# splitter_board.net
KiCad netlist of a schematic drawn in EAGLE
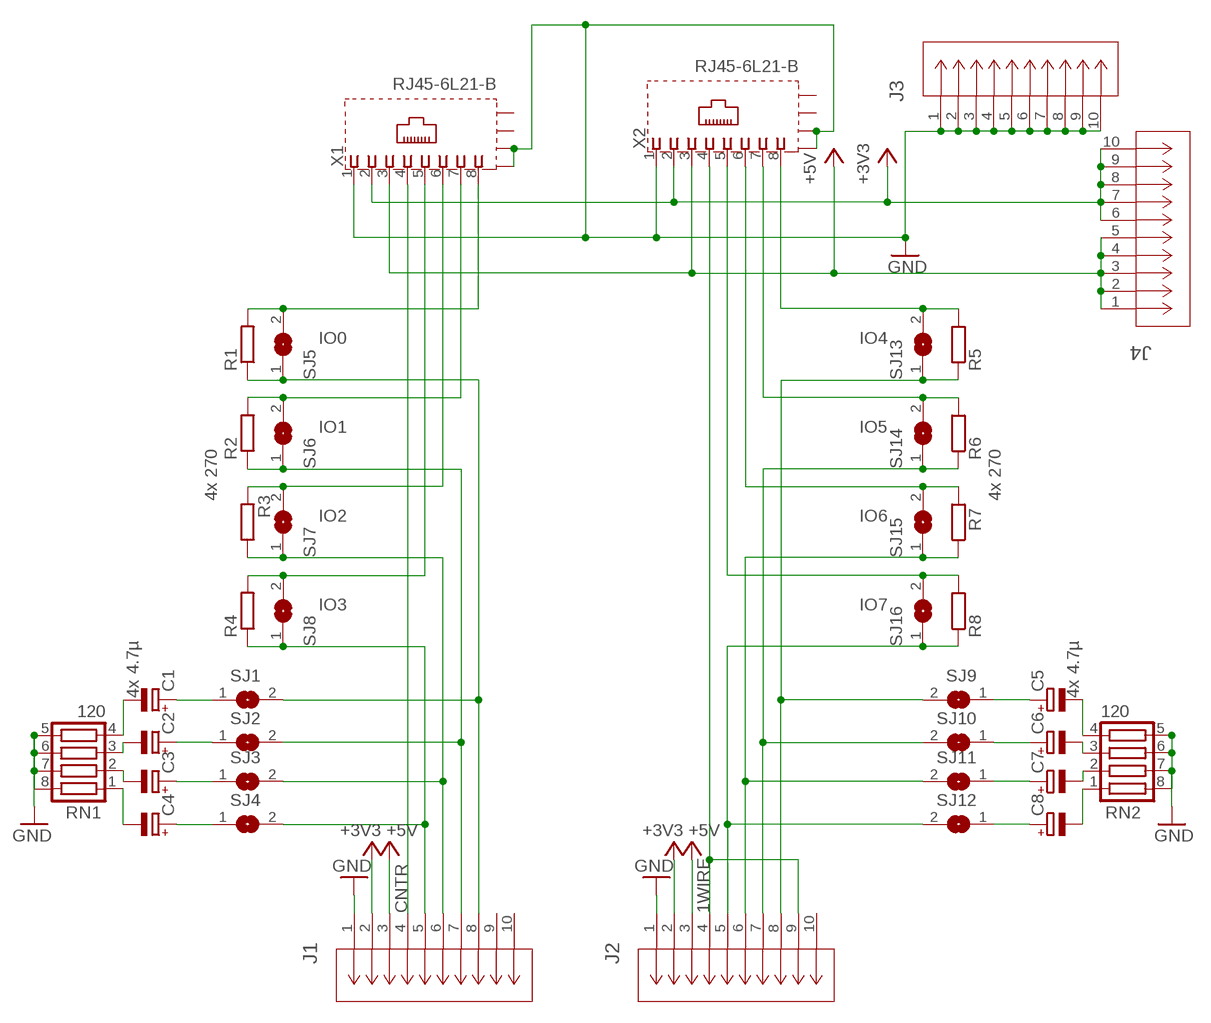
[diagram p0: schematic, sheet 1]

(export (version "E")
  (design (tool "Eeschema 10.0.6"))
  (components
    (comp (ref "C1")
      (value "4.7µ")
      (footprint "eagle-import:A_3216-18R")
      (libsource (lib "eagle-import") (part "CPOL-EUA/3216-18R"))
    )
    (comp (ref "C2")
      (value "4.7µ")
      (footprint "eagle-import:A_3216-18R")
      (libsource (lib "eagle-import") (part "CPOL-EUA/3216-18R"))
    )
    (comp (ref "C3")
      (value "4.7µ")
      (footprint "eagle-import:A_3216-18R")
      (libsource (lib "eagle-import") (part "CPOL-EUA/3216-18R"))
    )
    (comp (ref "C4")
      (value "4.7µ")
      (footprint "eagle-import:A_3216-18R")
      (libsource (lib "eagle-import") (part "CPOL-EUA/3216-18R"))
    )
    (comp (ref "C5")
      (value "4.7µ")
      (footprint "eagle-import:A_3216-18R")
      (libsource (lib "eagle-import") (part "CPOL-EUA/3216-18R"))
    )
    (comp (ref "C6")
      (value "4.7µ")
      (footprint "eagle-import:A_3216-18R")
      (libsource (lib "eagle-import") (part "CPOL-EUA/3216-18R"))
    )
    (comp (ref "C7")
      (value "4.7µ")
      (footprint "eagle-import:A_3216-18R")
      (libsource (lib "eagle-import") (part "CPOL-EUA/3216-18R"))
    )
    (comp (ref "C8")
      (value "4.7µ")
      (footprint "eagle-import:A_3216-18R")
      (libsource (lib "eagle-import") (part "CPOL-EUA/3216-18R"))
    )
    (comp (ref "J1")
      (value "250-410")
      (footprint "eagle-import:CONN_250-410_WAG")
      (fields (field (name "COPYRIGHT") "Copyright (C) 2022 Ultra Librarian. All rights reserved."))
      (libsource (lib "eagle-import") (part "250-410"))
    )
    (comp (ref "J2")
      (value "250-410")
      (footprint "eagle-import:CONN_250-410_WAG")
      (fields (field (name "COPYRIGHT") "Copyright (C) 2022 Ultra Librarian. All rights reserved."))
      (libsource (lib "eagle-import") (part "250-410"))
    )
    (comp (ref "J3")
      (value "250-410")
      (footprint "eagle-import:CONN_250-410_WAG")
      (fields (field (name "COPYRIGHT") "Copyright (C) 2022 Ultra Librarian. All rights reserved."))
      (libsource (lib "eagle-import") (part "250-410"))
    )
    (comp (ref "J4")
      (value "250-410")
      (footprint "eagle-import:CONN_250-410_WAG")
      (fields (field (name "COPYRIGHT") "Copyright (C) 2022 Ultra Librarian. All rights reserved."))
      (libsource (lib "eagle-import") (part "250-410"))
    )
    (comp (ref "R1")
      (value "270")
      (footprint "eagle-import:R0805")
      (libsource (lib "eagle-import") (part "R-EU_R0805"))
    )
    (comp (ref "R2")
      (value "270")
      (footprint "eagle-import:R0805")
      (libsource (lib "eagle-import") (part "R-EU_R0805"))
    )
    (comp (ref "R3")
      (value "270")
      (footprint "eagle-import:R0805")
      (libsource (lib "eagle-import") (part "R-EU_R0805"))
    )
    (comp (ref "R4")
      (value "270")
      (footprint "eagle-import:R0805")
      (libsource (lib "eagle-import") (part "R-EU_R0805"))
    )
    (comp (ref "R5")
      (value "270")
      (footprint "eagle-import:R0805")
      (libsource (lib "eagle-import") (part "R-EU_R0805"))
    )
    (comp (ref "R6")
      (value "270")
      (footprint "eagle-import:R0805")
      (libsource (lib "eagle-import") (part "R-EU_R0805"))
    )
    (comp (ref "R7")
      (value "270")
      (footprint "eagle-import:R0805")
      (libsource (lib "eagle-import") (part "R-EU_R0805"))
    )
    (comp (ref "R8")
      (value "270")
      (footprint "eagle-import:R0805")
      (libsource (lib "eagle-import") (part "R-EU_R0805"))
    )
    (comp (ref "RN1")
      (value "120")
      (footprint "eagle-import:CTS742C083")
      (libsource (lib "eagle-import") (part "CTS742C083"))
    )
    (comp (ref "RN2")
      (value "120")
      (footprint "eagle-import:CTS742C083")
      (libsource (lib "eagle-import") (part "CTS742C083"))
    )
    (comp (ref "SJ1") (value "SJ") (footprint "eagle-import:SJ") (libsource (lib "eagle-import") (part "SJ")))
    (comp (ref "SJ2") (value "SJ") (footprint "eagle-import:SJ") (libsource (lib "eagle-import") (part "SJ")))
    (comp (ref "SJ3") (value "SJ") (footprint "eagle-import:SJ") (libsource (lib "eagle-import") (part "SJ")))
    (comp (ref "SJ4") (value "SJ") (footprint "eagle-import:SJ") (libsource (lib "eagle-import") (part "SJ")))
    (comp (ref "SJ5") (value "SJ") (footprint "eagle-import:SJ") (libsource (lib "eagle-import") (part "SJ")))
    (comp (ref "SJ6") (value "SJ") (footprint "eagle-import:SJ") (libsource (lib "eagle-import") (part "SJ")))
    (comp (ref "SJ7") (value "SJ") (footprint "eagle-import:SJ") (libsource (lib "eagle-import") (part "SJ")))
    (comp (ref "SJ8") (value "SJ") (footprint "eagle-import:SJ") (libsource (lib "eagle-import") (part "SJ")))
    (comp (ref "SJ9") (value "SJ") (footprint "eagle-import:SJ") (libsource (lib "eagle-import") (part "SJ")))
    (comp (ref "SJ10")
      (value "SJ")
      (footprint "eagle-import:SJ")
      (libsource (lib "eagle-import") (part "SJ"))
    )
    (comp (ref "SJ11")
      (value "SJ")
      (footprint "eagle-import:SJ")
      (libsource (lib "eagle-import") (part "SJ"))
    )
    (comp (ref "SJ12")
      (value "SJ")
      (footprint "eagle-import:SJ")
      (libsource (lib "eagle-import") (part "SJ"))
    )
    (comp (ref "SJ13")
      (value "SJ")
      (footprint "eagle-import:SJ")
      (libsource (lib "eagle-import") (part "SJ"))
    )
    (comp (ref "SJ14")
      (value "SJ")
      (footprint "eagle-import:SJ")
      (libsource (lib "eagle-import") (part "SJ"))
    )
    (comp (ref "SJ15")
      (value "SJ")
      (footprint "eagle-import:SJ")
      (libsource (lib "eagle-import") (part "SJ"))
    )
    (comp (ref "SJ16")
      (value "SJ")
      (footprint "eagle-import:SJ")
      (libsource (lib "eagle-import") (part "SJ"))
    )
    (comp (ref "X1")
      (value "RJ45-6L21-B")
      (footprint "eagle-import:RJ45-SHIELD1")
      (libsource (lib "eagle-import") (part "RJ4521-B-6L"))
    )
    (comp (ref "X2")
      (value "RJ45-6L21-B")
      (footprint "eagle-import:RJ45-SHIELD1")
      (libsource (lib "eagle-import") (part "RJ4521-B-6L"))
    )
  )
  (nets
    (net (code "1") (name "+3V3") (class "Default")
      (node (ref "J1") (pin "2") (pinfunction "2_2") (pintype "passive"))
      (node (ref "J2") (pin "2") (pinfunction "2_2") (pintype "passive"))
      (node (ref "J4") (pin "10") (pinfunction "10_10") (pintype "passive"))
      (node (ref "J4") (pin "6") (pinfunction "6_6") (pintype "passive"))
      (node (ref "J4") (pin "7") (pinfunction "7_7") (pintype "passive"))
      (node (ref "J4") (pin "8") (pinfunction "8_8") (pintype "passive"))
      (node (ref "J4") (pin "9") (pinfunction "9_9") (pintype "passive"))
      (node (ref "X1") (pin "2") (pinfunction "2_2") (pintype "passive"))
      (node (ref "X2") (pin "2") (pinfunction "2_2") (pintype "passive"))
    )
    (net (code "2") (name "+5V") (class "Default")
      (node (ref "J1") (pin "3") (pinfunction "3_3") (pintype "passive"))
      (node (ref "J2") (pin "3") (pinfunction "3_3") (pintype "passive"))
      (node (ref "J4") (pin "1") (pinfunction "1_1") (pintype "passive"))
      (node (ref "J4") (pin "2") (pinfunction "2_2") (pintype "passive"))
      (node (ref "J4") (pin "3") (pinfunction "3_3") (pintype "passive"))
      (node (ref "J4") (pin "4") (pinfunction "4_4") (pintype "passive"))
      (node (ref "J4") (pin "5") (pinfunction "5_5") (pintype "passive"))
      (node (ref "X1") (pin "3") (pinfunction "3_3") (pintype "passive"))
      (node (ref "X2") (pin "3") (pinfunction "3_3") (pintype "passive"))
    )
    (net (code "3") (name "/1WIRE") (class "Default")
      (node (ref "J2") (pin "4") (pinfunction "4_4") (pintype "passive"))
      (node (ref "J2") (pin "9") (pinfunction "9_9") (pintype "passive"))
      (node (ref "X2") (pin "4") (pinfunction "4_4") (pintype "passive"))
    )
    (net (code "4") (name "/CNTR") (class "Default")
      (node (ref "J1") (pin "4") (pinfunction "4_4") (pintype "passive"))
      (node (ref "X1") (pin "4") (pinfunction "4_4") (pintype "passive"))
    )
    (net (code "5") (name "/IO0") (class "Default")
      (node (ref "R1") (pin "2") (pinfunction "2_2") (pintype "passive"))
      (node (ref "SJ5") (pin "2") (pinfunction "2_2") (pintype "passive"))
      (node (ref "X1") (pin "8") (pinfunction "8_8") (pintype "passive"))
    )
    (net (code "6") (name "/IO1") (class "Default")
      (node (ref "R2") (pin "2") (pinfunction "2_2") (pintype "passive"))
      (node (ref "SJ6") (pin "2") (pinfunction "2_2") (pintype "passive"))
      (node (ref "X1") (pin "7") (pinfunction "7_7") (pintype "passive"))
    )
    (net (code "7") (name "/IO2") (class "Default")
      (node (ref "R3") (pin "2") (pinfunction "2_2") (pintype "passive"))
      (node (ref "SJ7") (pin "2") (pinfunction "2_2") (pintype "passive"))
      (node (ref "X1") (pin "6") (pinfunction "6_6") (pintype "passive"))
    )
    (net (code "8") (name "/IO3") (class "Default")
      (node (ref "R4") (pin "2") (pinfunction "2_2") (pintype "passive"))
      (node (ref "SJ8") (pin "2") (pinfunction "2_2") (pintype "passive"))
      (node (ref "X1") (pin "5") (pinfunction "5_5") (pintype "passive"))
    )
    (net (code "9") (name "/IO4") (class "Default")
      (node (ref "R5") (pin "2") (pinfunction "2_2") (pintype "passive"))
      (node (ref "SJ13") (pin "2") (pinfunction "2_2") (pintype "passive"))
      (node (ref "X2") (pin "8") (pinfunction "8_8") (pintype "passive"))
    )
    (net (code "10") (name "/IO5") (class "Default")
      (node (ref "R6") (pin "2") (pinfunction "2_2") (pintype "passive"))
      (node (ref "SJ14") (pin "2") (pinfunction "2_2") (pintype "passive"))
      (node (ref "X2") (pin "7") (pinfunction "7_7") (pintype "passive"))
    )
    (net (code "11") (name "/IO6") (class "Default")
      (node (ref "R7") (pin "2") (pinfunction "2_2") (pintype "passive"))
      (node (ref "SJ15") (pin "2") (pinfunction "2_2") (pintype "passive"))
      (node (ref "X2") (pin "6") (pinfunction "6_6") (pintype "passive"))
    )
    (net (code "12") (name "/IO7") (class "Default")
      (node (ref "R8") (pin "2") (pinfunction "2_2") (pintype "passive"))
      (node (ref "SJ16") (pin "2") (pinfunction "2_2") (pintype "passive"))
      (node (ref "X2") (pin "5") (pinfunction "5_5") (pintype "passive"))
    )
    (net (code "13") (name "GND") (class "Default")
      (node (ref "J1") (pin "1") (pinfunction "1_1") (pintype "passive"))
      (node (ref "J2") (pin "1") (pinfunction "1_1") (pintype "passive"))
      (node (ref "J3") (pin "1") (pinfunction "1_1") (pintype "passive"))
      (node (ref "J3") (pin "10") (pinfunction "10_10") (pintype "passive"))
      (node (ref "J3") (pin "2") (pinfunction "2_2") (pintype "passive"))
      (node (ref "J3") (pin "3") (pinfunction "3_3") (pintype "passive"))
      (node (ref "J3") (pin "4") (pinfunction "4_4") (pintype "passive"))
      (node (ref "J3") (pin "5") (pinfunction "5_5") (pintype "passive"))
      (node (ref "J3") (pin "6") (pinfunction "6_6") (pintype "passive"))
      (node (ref "J3") (pin "7") (pinfunction "7_7") (pintype "passive"))
      (node (ref "J3") (pin "8") (pinfunction "8_8") (pintype "passive"))
      (node (ref "J3") (pin "9") (pinfunction "9_9") (pintype "passive"))
      (node (ref "RN1") (pin "5") (pinfunction "5_5") (pintype "passive"))
      (node (ref "RN1") (pin "6") (pinfunction "6_6") (pintype "passive"))
      (node (ref "RN1") (pin "7") (pinfunction "7_7") (pintype "passive"))
      (node (ref "RN1") (pin "8") (pinfunction "8_8") (pintype "passive"))
      (node (ref "RN2") (pin "5") (pinfunction "5_5") (pintype "passive"))
      (node (ref "RN2") (pin "6") (pinfunction "6_6") (pintype "passive"))
      (node (ref "RN2") (pin "7") (pinfunction "7_7") (pintype "passive"))
      (node (ref "RN2") (pin "8") (pinfunction "8_8") (pintype "passive"))
      (node (ref "X1") (pin "1") (pinfunction "1_1") (pintype "passive"))
      (node (ref "X1") (pin "S1") (pinfunction "S_S1") (pintype "passive"))
      (node (ref "X1") (pin "S2") (pinfunction "S_S2") (pintype "passive"))
      (node (ref "X2") (pin "1") (pinfunction "1_1") (pintype "passive"))
      (node (ref "X2") (pin "S1") (pinfunction "S_S1") (pintype "passive"))
      (node (ref "X2") (pin "S2") (pinfunction "S_S2") (pintype "passive"))
    )
    (net (code "14") (name "Net-(C1-Pad+)") (class "Default")
      (node (ref "C1") (pin "+") (pinfunction "+_+") (pintype "passive"))
      (node (ref "SJ1") (pin "1") (pinfunction "1_1") (pintype "passive"))
    )
    (net (code "15") (name "Net-(C1-Pad-)") (class "Default")
      (node (ref "C1") (pin "-") (pinfunction "-_-") (pintype "passive"))
      (node (ref "RN1") (pin "4") (pinfunction "4_4") (pintype "passive"))
    )
    (net (code "16") (name "Net-(C2-Pad+)") (class "Default")
      (node (ref "C2") (pin "+") (pinfunction "+_+") (pintype "passive"))
      (node (ref "SJ2") (pin "1") (pinfunction "1_1") (pintype "passive"))
    )
    (net (code "17") (name "Net-(C2-Pad-)") (class "Default")
      (node (ref "C2") (pin "-") (pinfunction "-_-") (pintype "passive"))
      (node (ref "RN1") (pin "3") (pinfunction "3_3") (pintype "passive"))
    )
    (net (code "18") (name "Net-(C3-Pad+)") (class "Default")
      (node (ref "C3") (pin "+") (pinfunction "+_+") (pintype "passive"))
      (node (ref "SJ3") (pin "1") (pinfunction "1_1") (pintype "passive"))
    )
    (net (code "19") (name "Net-(C3-Pad-)") (class "Default")
      (node (ref "C3") (pin "-") (pinfunction "-_-") (pintype "passive"))
      (node (ref "RN1") (pin "2") (pinfunction "2_2") (pintype "passive"))
    )
    (net (code "20") (name "Net-(C4-Pad+)") (class "Default")
      (node (ref "C4") (pin "+") (pinfunction "+_+") (pintype "passive"))
      (node (ref "SJ4") (pin "1") (pinfunction "1_1") (pintype "passive"))
    )
    (net (code "21") (name "Net-(C4-Pad-)") (class "Default")
      (node (ref "C4") (pin "-") (pinfunction "-_-") (pintype "passive"))
      (node (ref "RN1") (pin "1") (pinfunction "1_1") (pintype "passive"))
    )
    (net (code "22") (name "Net-(C5-Pad+)") (class "Default")
      (node (ref "C5") (pin "+") (pinfunction "+_+") (pintype "passive"))
      (node (ref "SJ9") (pin "1") (pinfunction "1_1") (pintype "passive"))
    )
    (net (code "23") (name "Net-(C5-Pad-)") (class "Default")
      (node (ref "C5") (pin "-") (pinfunction "-_-") (pintype "passive"))
      (node (ref "RN2") (pin "4") (pinfunction "4_4") (pintype "passive"))
    )
    (net (code "24") (name "Net-(C6-Pad+)") (class "Default")
      (node (ref "C6") (pin "+") (pinfunction "+_+") (pintype "passive"))
      (node (ref "SJ10") (pin "1") (pinfunction "1_1") (pintype "passive"))
    )
    (net (code "25") (name "Net-(C6-Pad-)") (class "Default")
      (node (ref "C6") (pin "-") (pinfunction "-_-") (pintype "passive"))
      (node (ref "RN2") (pin "3") (pinfunction "3_3") (pintype "passive"))
    )
    (net (code "26") (name "Net-(C7-Pad+)") (class "Default")
      (node (ref "C7") (pin "+") (pinfunction "+_+") (pintype "passive"))
      (node (ref "SJ11") (pin "1") (pinfunction "1_1") (pintype "passive"))
    )
    (net (code "27") (name "Net-(C7-Pad-)") (class "Default")
      (node (ref "C7") (pin "-") (pinfunction "-_-") (pintype "passive"))
      (node (ref "RN2") (pin "2") (pinfunction "2_2") (pintype "passive"))
    )
    (net (code "28") (name "Net-(C8-Pad+)") (class "Default")
      (node (ref "C8") (pin "+") (pinfunction "+_+") (pintype "passive"))
      (node (ref "SJ12") (pin "1") (pinfunction "1_1") (pintype "passive"))
    )
    (net (code "29") (name "Net-(C8-Pad-)") (class "Default")
      (node (ref "C8") (pin "-") (pinfunction "-_-") (pintype "passive"))
      (node (ref "RN2") (pin "1") (pinfunction "1_1") (pintype "passive"))
    )
    (net (code "30") (name "Net-(J1-Pad5)") (class "Default")
      (node (ref "J1") (pin "5") (pinfunction "5_5") (pintype "passive"))
      (node (ref "R4") (pin "1") (pinfunction "1_1") (pintype "passive"))
      (node (ref "SJ4") (pin "2") (pinfunction "2_2") (pintype "passive"))
      (node (ref "SJ8") (pin "1") (pinfunction "1_1") (pintype "passive"))
    )
    (net (code "31") (name "Net-(J1-Pad6)") (class "Default")
      (node (ref "J1") (pin "6") (pinfunction "6_6") (pintype "passive"))
      (node (ref "R3") (pin "1") (pinfunction "1_1") (pintype "passive"))
      (node (ref "SJ3") (pin "2") (pinfunction "2_2") (pintype "passive"))
      (node (ref "SJ7") (pin "1") (pinfunction "1_1") (pintype "passive"))
    )
    (net (code "32") (name "Net-(J1-Pad7)") (class "Default")
      (node (ref "J1") (pin "7") (pinfunction "7_7") (pintype "passive"))
      (node (ref "R2") (pin "1") (pinfunction "1_1") (pintype "passive"))
      (node (ref "SJ2") (pin "2") (pinfunction "2_2") (pintype "passive"))
      (node (ref "SJ6") (pin "1") (pinfunction "1_1") (pintype "passive"))
    )
    (net (code "33") (name "Net-(J1-Pad8)") (class "Default")
      (node (ref "J1") (pin "8") (pinfunction "8_8") (pintype "passive"))
      (node (ref "R1") (pin "1") (pinfunction "1_1") (pintype "passive"))
      (node (ref "SJ1") (pin "2") (pinfunction "2_2") (pintype "passive"))
      (node (ref "SJ5") (pin "1") (pinfunction "1_1") (pintype "passive"))
    )
    (net (code "34") (name "Net-(J2-Pad5)") (class "Default")
      (node (ref "J2") (pin "5") (pinfunction "5_5") (pintype "passive"))
      (node (ref "R8") (pin "1") (pinfunction "1_1") (pintype "passive"))
      (node (ref "SJ12") (pin "2") (pinfunction "2_2") (pintype "passive"))
      (node (ref "SJ16") (pin "1") (pinfunction "1_1") (pintype "passive"))
    )
    (net (code "35") (name "Net-(J2-Pad6)") (class "Default")
      (node (ref "J2") (pin "6") (pinfunction "6_6") (pintype "passive"))
      (node (ref "R7") (pin "1") (pinfunction "1_1") (pintype "passive"))
      (node (ref "SJ11") (pin "2") (pinfunction "2_2") (pintype "passive"))
      (node (ref "SJ15") (pin "1") (pinfunction "1_1") (pintype "passive"))
    )
    (net (code "36") (name "Net-(J2-Pad7)") (class "Default")
      (node (ref "J2") (pin "7") (pinfunction "7_7") (pintype "passive"))
      (node (ref "R6") (pin "1") (pinfunction "1_1") (pintype "passive"))
      (node (ref "SJ10") (pin "2") (pinfunction "2_2") (pintype "passive"))
      (node (ref "SJ14") (pin "1") (pinfunction "1_1") (pintype "passive"))
    )
    (net (code "37") (name "Net-(J2-Pad8)") (class "Default")
      (node (ref "J2") (pin "8") (pinfunction "8_8") (pintype "passive"))
      (node (ref "R5") (pin "1") (pinfunction "1_1") (pintype "passive"))
      (node (ref "SJ13") (pin "1") (pinfunction "1_1") (pintype "passive"))
      (node (ref "SJ9") (pin "2") (pinfunction "2_2") (pintype "passive"))
    )
    (net (code "38") (name "unconnected-(J1-Pad9)") (class "Default")
      (node (ref "J1") (pin "9") (pinfunction "9_9") (pintype "passive"))
    )
    (net (code "39") (name "unconnected-(J1-Pad10)") (class "Default")
      (node (ref "J1") (pin "10") (pinfunction "10_10") (pintype "passive"))
    )
    (net (code "40") (name "unconnected-(J2-Pad10)") (class "Default")
      (node (ref "J2") (pin "10") (pinfunction "10_10") (pintype "passive"))
    )
    (net (code "41") (name "unconnected-(X1-S-PadS3)") (class "Default")
      (node (ref "X1") (pin "S3") (pinfunction "S_S3") (pintype "passive"))
    )
    (net (code "42") (name "unconnected-(X1-S-PadS4)") (class "Default")
      (node (ref "X1") (pin "S4") (pinfunction "S_S4") (pintype "passive"))
    )
    (net (code "43") (name "unconnected-(X2-S-PadS3)") (class "Default")
      (node (ref "X2") (pin "S3") (pinfunction "S_S3") (pintype "passive"))
    )
    (net (code "44") (name "unconnected-(X2-S-PadS4)") (class "Default")
      (node (ref "X2") (pin "S4") (pinfunction "S_S4") (pintype "passive"))
    )
  )
)
